# PhonePresent.net
KiCad netlist of a schematic drawn in Altium Designer
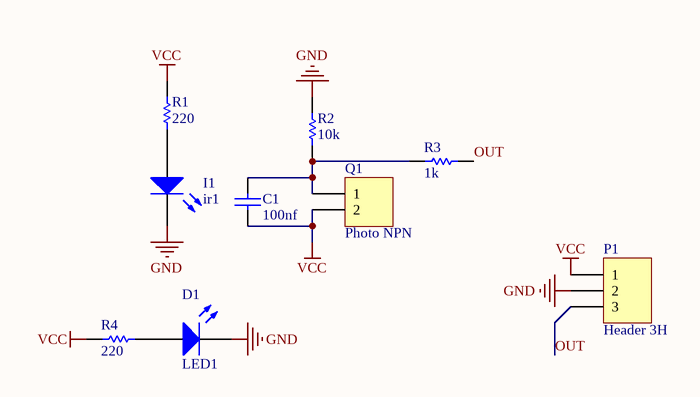
[diagram p0: PhonePresent.SchDoc]

(export (version "E")
  (design (tool "Eeschema 10.0.6"))
  (components
    (comp (ref "C1")
      (value "100nf")
      (footprint "6-0805_M")
      (description "Capacitor")
      (fields (field (name "Comment") "Cap") (field (name "PUBLISHER") "Altium Limited"))
      (libsource (lib "Miscellaneous Devices") (part "Cap"))
    )
    (comp (ref "D1")
      (value "LED1")
      (footprint "hdr1x2")
      (description "Typical RED GaAs LED")
      (fields (field (name "PUBLISHER") "Altium Limited"))
      (libsource (lib "Miscellaneous Devices") (part "LED1"))
    )
    (comp (ref "I1")
      (value "ir1")
      (footprint "HDR1X2")
      (description "Typical INFRARED GaAs LED")
      (fields (field (name "PUBLISHER") "Altium Limited"))
      (libsource (lib "Miscellaneous Devices") (part "LED0"))
    )
    (comp (ref "P1")
      (value "Header 3H")
      (footprint "HDR1X3H")
      (description "Header, 3-Pin, Right Angle")
      (fields (field (name "PUBLISHER") "Altium Limited"))
      (libsource (lib "Miscellaneous Connectors") (part "Header 3H"))
    )
    (comp (ref "Q1")
      (value "Photo NPN")
      (footprint "HDR1X2")
      (description "Header, 2-Pin")
      (fields (field (name "PUBLISHER") "Altium Limited"))
      (libsource (lib "Miscellaneous Connectors") (part "Header 2"))
    )
    (comp (ref "R1")
      (value "220")
      (footprint "6-0805_M")
      (description "Resistor")
      (fields (field (name "PUBLISHER") "Altium Limited"))
      (libsource (lib "Miscellaneous Devices") (part "Res1"))
    )
    (comp (ref "R2")
      (value "10k")
      (footprint "6-0805_M")
      (description "Resistor")
      (fields (field (name "Comment") "10K") (field (name "PUBLISHER") "Altium Limited"))
      (libsource (lib "Miscellaneous Devices") (part "Res1"))
    )
    (comp (ref "R3")
      (value "1k")
      (footprint "6-0805_M")
      (description "Resistor")
      (fields (field (name "Comment") "1K") (field (name "PUBLISHER") "Altium Limited"))
      (libsource (lib "Miscellaneous Devices") (part "Res1"))
    )
    (comp (ref "R4")
      (value "220")
      (footprint "6-0805_M")
      (description "Resistor")
      (fields (field (name "PUBLISHER") "Altium Limited"))
      (libsource (lib "Miscellaneous Devices") (part "Res1"))
    )
  )
  (nets
    (net (code "1") (name "/OUT") (class "Default")
      (node (ref "P1") (pin "3") (pinfunction "3_3") (pintype "passive"))
      (node (ref "R3") (pin "2") (pinfunction "2_2") (pintype "passive"))
    )
    (net (code "2") (name "GND") (class "Default")
      (node (ref "D1") (pin "2") (pinfunction "K_2") (pintype "passive"))
      (node (ref "I1") (pin "2") (pinfunction "K_2") (pintype "passive"))
      (node (ref "P1") (pin "2") (pinfunction "2_2") (pintype "passive"))
      (node (ref "R2") (pin "1") (pinfunction "1_1") (pintype "passive"))
    )
    (net (code "3") (name "Net-(C1-Pad1)") (class "Default")
      (node (ref "C1") (pin "1") (pinfunction "1_1") (pintype "passive"))
      (node (ref "Q1") (pin "1") (pinfunction "1_1") (pintype "passive"))
      (node (ref "R2") (pin "2") (pinfunction "2_2") (pintype "passive"))
      (node (ref "R3") (pin "1") (pinfunction "1_1") (pintype "passive"))
    )
    (net (code "4") (name "Net-(D1-A)") (class "Default")
      (node (ref "D1") (pin "1") (pinfunction "A_1") (pintype "passive"))
      (node (ref "R4") (pin "2") (pinfunction "2_2") (pintype "passive"))
    )
    (net (code "5") (name "Net-(I1-A)") (class "Default")
      (node (ref "I1") (pin "1") (pinfunction "A_1") (pintype "passive"))
      (node (ref "R1") (pin "2") (pinfunction "2_2") (pintype "passive"))
    )
    (net (code "6") (name "VCC") (class "Default")
      (node (ref "C1") (pin "2") (pinfunction "2_2") (pintype "passive"))
      (node (ref "P1") (pin "1") (pinfunction "1_1") (pintype "passive"))
      (node (ref "Q1") (pin "2") (pinfunction "2_2") (pintype "passive"))
      (node (ref "R1") (pin "1") (pinfunction "1_1") (pintype "passive"))
      (node (ref "R4") (pin "1") (pinfunction "1_1") (pintype "passive"))
    )
  )
)
